# in4_single_v0_2_revB.net
KiCad netlist of a schematic drawn in EAGLE
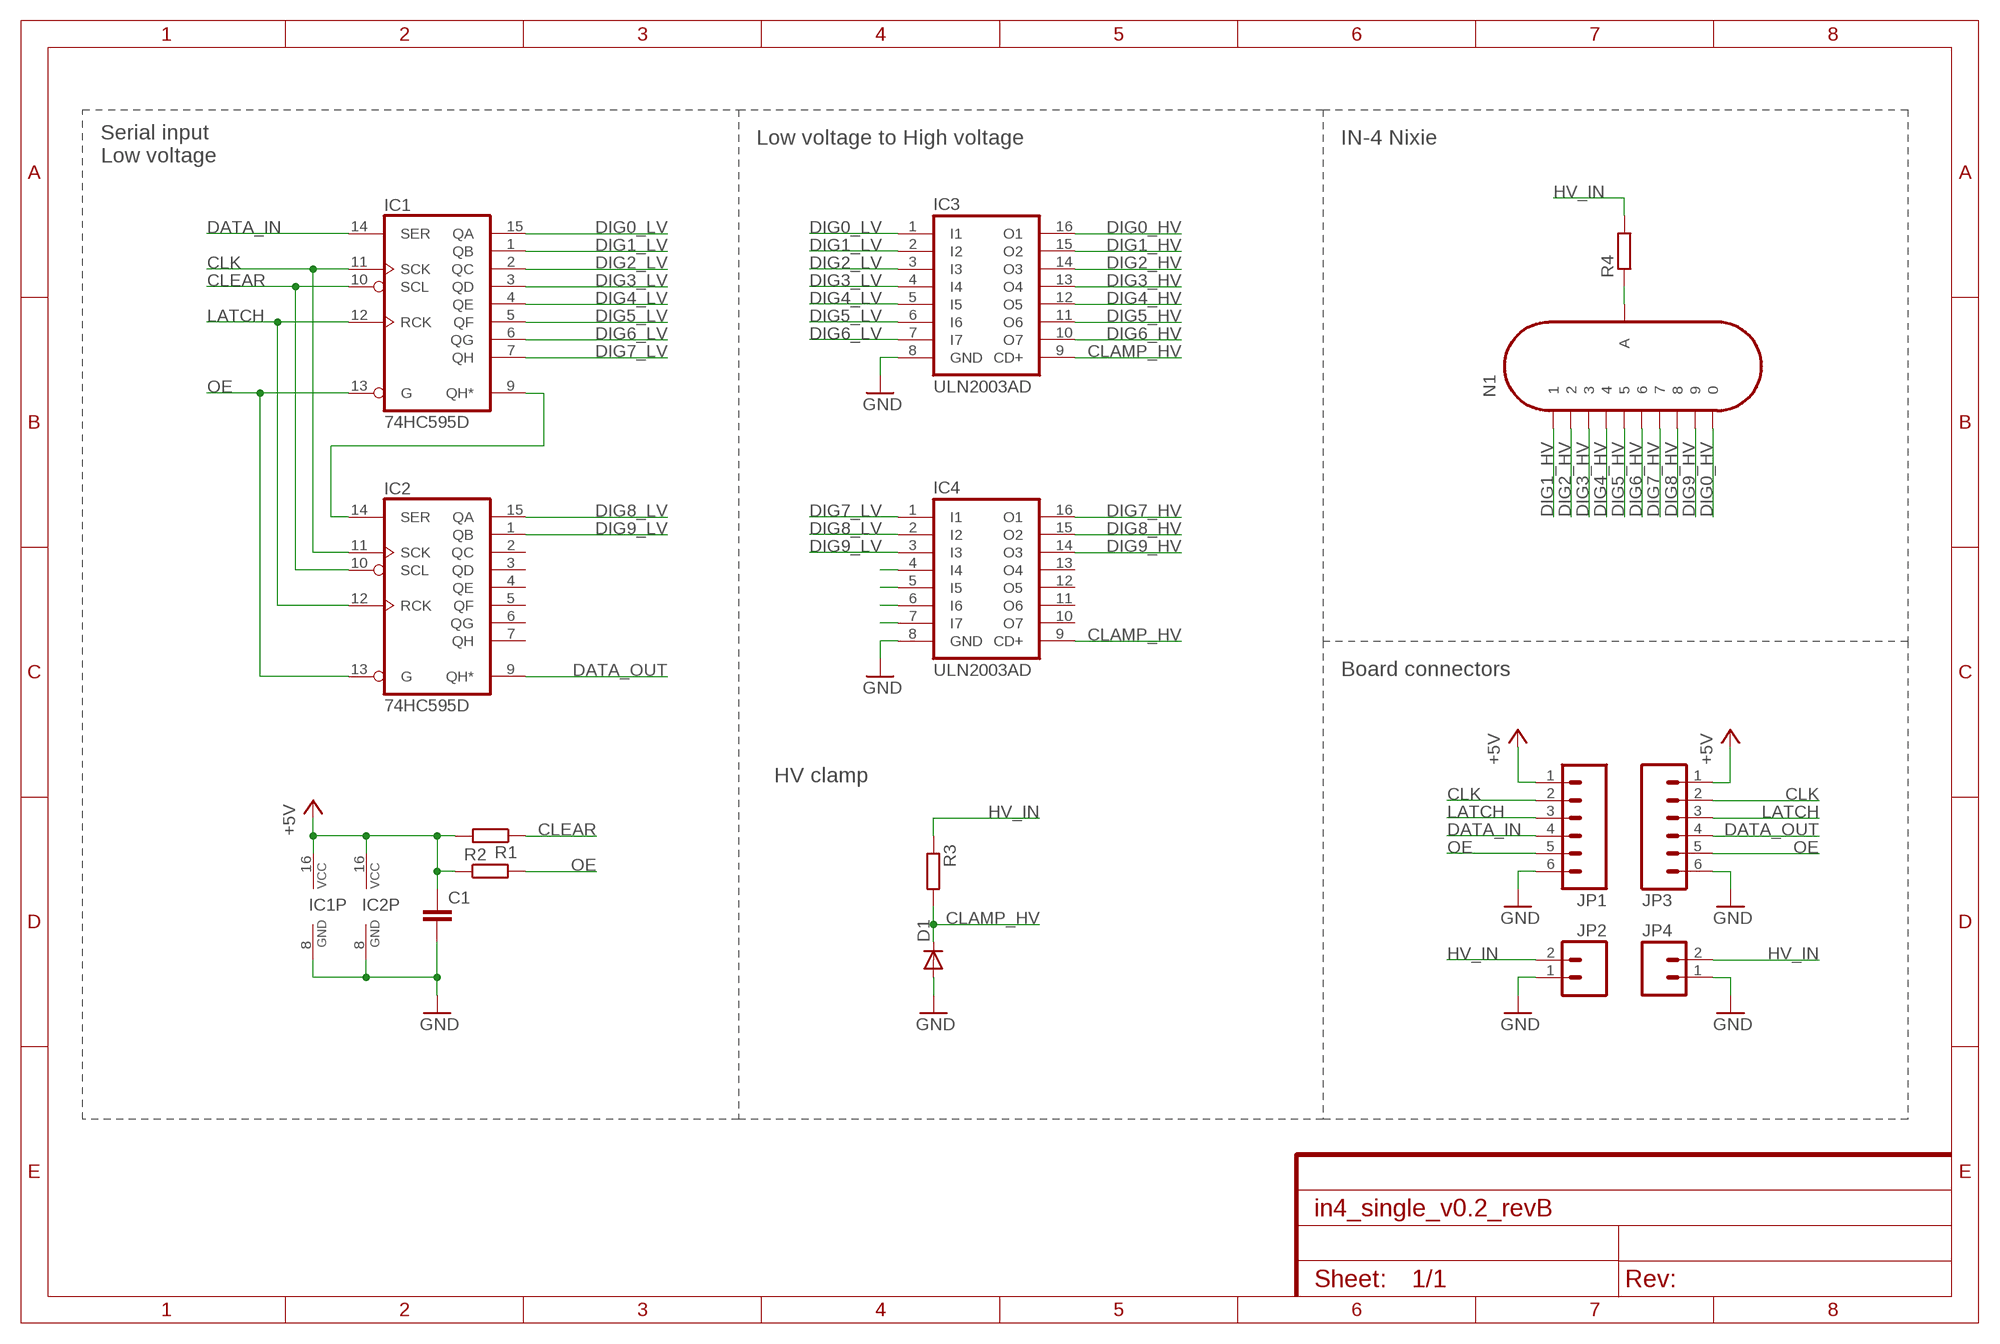
[diagram p0: schematic, sheet 1]

(export (version "E")
  (design (tool "Eeschema 10.0.6"))
  (components
    (comp (ref "C1")
      (value "C-EUC0805")
      (footprint "eagle-import:C0805")
      (libsource (lib "eagle-import") (part "C-EUC0805"))
    )
    (comp (ref "D1")
      (value "DIODE-SOD-123")
      (footprint "eagle-import:SOD-123")
      (libsource (lib "eagle-import") (part "DIODE-SOD-123"))
    )
    (comp (ref "IC1")
      (value "74HC595D")
      (footprint "eagle-import:SO16")
      (libsource (lib "eagle-import") (part "74595DHC"))
    )
    (comp (ref "IC2")
      (value "74HC595D")
      (footprint "eagle-import:SO16")
      (libsource (lib "eagle-import") (part "74595DHC"))
    )
    (comp (ref "IC3")
      (value "ULN2003AD")
      (footprint "eagle-import:SO16")
      (libsource (lib "eagle-import") (part "ULN2003AD"))
    )
    (comp (ref "IC4")
      (value "ULN2003AD")
      (footprint "eagle-import:SO16")
      (libsource (lib "eagle-import") (part "ULN2003AD"))
    )
    (comp (ref "JP1")
      (value "M06NO_SILK_FEMALE_PTH")
      (footprint "eagle-import:1X06_NO_SILK")
      (libsource (lib "eagle-import") (part "M06NO_SILK_FEMALE_PTH"))
    )
    (comp (ref "JP2")
      (value "M021X02_NO_SILK")
      (footprint "eagle-import:1X02_NO_SILK")
      (libsource (lib "eagle-import") (part "M021X02_NO_SILK"))
    )
    (comp (ref "JP3")
      (value "M06NO_SILK_FEMALE_PTH")
      (footprint "eagle-import:1X06_NO_SILK")
      (libsource (lib "eagle-import") (part "M06NO_SILK_FEMALE_PTH"))
    )
    (comp (ref "JP4")
      (value "M021X02_NO_SILK")
      (footprint "eagle-import:1X02_NO_SILK")
      (libsource (lib "eagle-import") (part "M021X02_NO_SILK"))
    )
    (comp (ref "N1")
      (value "IN-4")
      (footprint "eagle-import:IN-4")
      (libsource (lib "eagle-import") (part "IN-4"))
    )
    (comp (ref "R1")
      (value "R-EU_R0805")
      (footprint "eagle-import:R0805")
      (libsource (lib "eagle-import") (part "R-EU_R0805"))
    )
    (comp (ref "R2")
      (value "R-EU_R0805")
      (footprint "eagle-import:R0805")
      (libsource (lib "eagle-import") (part "R-EU_R0805"))
    )
    (comp (ref "R3")
      (value "R-EU_R0805")
      (footprint "eagle-import:R0805")
      (libsource (lib "eagle-import") (part "R-EU_R0805"))
    )
    (comp (ref "R4")
      (value "R-EU_R1210")
      (footprint "eagle-import:R1210")
      (libsource (lib "eagle-import") (part "resistor_R-EU_R1210"))
    )
  )
  (nets
    (net (code "1") (name "+5V") (class "Default")
      (node (ref "C1") (pin "1") (pinfunction "1_1") (pintype "passive"))
      (node (ref "IC1") (pin "16") (pinfunction "VCC_16") (pintype "power_in"))
      (node (ref "IC2") (pin "16") (pinfunction "VCC_16") (pintype "power_in"))
      (node (ref "JP1") (pin "1") (pinfunction "1_1") (pintype "passive"))
      (node (ref "JP3") (pin "1") (pinfunction "1_1") (pintype "passive"))
      (node (ref "R1") (pin "2") (pinfunction "2_2") (pintype "passive"))
      (node (ref "R2") (pin "1") (pinfunction "1_1") (pintype "passive"))
    )
    (net (code "2") (name "/CLAMP_HV") (class "Default")
      (node (ref "D1") (pin "C") (pinfunction "C_C") (pintype "passive"))
      (node (ref "IC3") (pin "9") (pinfunction "CD+_9") (pintype "passive"))
      (node (ref "IC4") (pin "9") (pinfunction "CD+_9") (pintype "passive"))
      (node (ref "R3") (pin "2") (pinfunction "2_2") (pintype "passive"))
    )
    (net (code "3") (name "/CLEAR") (class "Default")
      (node (ref "IC1") (pin "10") (pinfunction "SCL_10") (pintype "input"))
      (node (ref "IC2") (pin "10") (pinfunction "SCL_10") (pintype "input"))
      (node (ref "R1") (pin "1") (pinfunction "1_1") (pintype "passive"))
    )
    (net (code "4") (name "/CLK") (class "Default")
      (node (ref "IC1") (pin "11") (pinfunction "SCK_11") (pintype "input"))
      (node (ref "IC2") (pin "11") (pinfunction "SCK_11") (pintype "input"))
      (node (ref "JP1") (pin "2") (pinfunction "2_2") (pintype "passive"))
      (node (ref "JP3") (pin "2") (pinfunction "2_2") (pintype "passive"))
    )
    (net (code "5") (name "/DATA_IN") (class "Default")
      (node (ref "IC1") (pin "14") (pinfunction "SER_14") (pintype "input"))
      (node (ref "JP1") (pin "4") (pinfunction "4_4") (pintype "passive"))
    )
    (net (code "6") (name "/DATA_OUT") (class "Default")
      (node (ref "IC2") (pin "9") (pinfunction "QH*_9") (pintype "tri_state"))
      (node (ref "JP3") (pin "4") (pinfunction "4_4") (pintype "passive"))
    )
    (net (code "7") (name "/DIG0_HV") (class "Default")
      (node (ref "IC3") (pin "16") (pinfunction "O1_16") (pintype "open_collector"))
      (node (ref "N1") (pin "8") (pinfunction "0_8") (pintype "bidirectional"))
    )
    (net (code "8") (name "/DIG0_LV") (class "Default")
      (node (ref "IC1") (pin "15") (pinfunction "QA_15") (pintype "tri_state"))
      (node (ref "IC3") (pin "1") (pinfunction "I1_1") (pintype "input"))
    )
    (net (code "9") (name "/DIG1_HV") (class "Default")
      (node (ref "IC3") (pin "15") (pinfunction "O2_15") (pintype "open_collector"))
      (node (ref "N1") (pin "14") (pinfunction "1_14") (pintype "bidirectional"))
    )
    (net (code "10") (name "/DIG1_LV") (class "Default")
      (node (ref "IC1") (pin "1") (pinfunction "QB_1") (pintype "tri_state"))
      (node (ref "IC3") (pin "2") (pinfunction "I2_2") (pintype "input"))
    )
    (net (code "11") (name "/DIG2_HV") (class "Default")
      (node (ref "IC3") (pin "14") (pinfunction "O3_14") (pintype "open_collector"))
      (node (ref "N1") (pin "9") (pinfunction "2_9") (pintype "bidirectional"))
    )
    (net (code "12") (name "/DIG2_LV") (class "Default")
      (node (ref "IC1") (pin "2") (pinfunction "QC_2") (pintype "tri_state"))
      (node (ref "IC3") (pin "3") (pinfunction "I3_3") (pintype "input"))
    )
    (net (code "13") (name "/DIG3_HV") (class "Default")
      (node (ref "IC3") (pin "13") (pinfunction "O4_13") (pintype "open_collector"))
      (node (ref "N1") (pin "11") (pinfunction "3_11") (pintype "bidirectional"))
    )
    (net (code "14") (name "/DIG3_LV") (class "Default")
      (node (ref "IC1") (pin "3") (pinfunction "QD_3") (pintype "tri_state"))
      (node (ref "IC3") (pin "4") (pinfunction "I4_4") (pintype "input"))
    )
    (net (code "15") (name "/DIG4_HV") (class "Default")
      (node (ref "IC3") (pin "12") (pinfunction "O5_12") (pintype "open_collector"))
      (node (ref "N1") (pin "1") (pinfunction "4_1") (pintype "bidirectional"))
    )
    (net (code "16") (name "/DIG4_LV") (class "Default")
      (node (ref "IC1") (pin "4") (pinfunction "QE_4") (pintype "tri_state"))
      (node (ref "IC3") (pin "5") (pinfunction "I5_5") (pintype "input"))
    )
    (net (code "17") (name "/DIG5_HV") (class "Default")
      (node (ref "IC3") (pin "11") (pinfunction "O6_11") (pintype "open_collector"))
      (node (ref "N1") (pin "12") (pinfunction "5_12") (pintype "bidirectional"))
    )
    (net (code "18") (name "/DIG5_LV") (class "Default")
      (node (ref "IC1") (pin "5") (pinfunction "QF_5") (pintype "tri_state"))
      (node (ref "IC3") (pin "6") (pinfunction "I6_6") (pintype "input"))
    )
    (net (code "19") (name "/DIG6_HV") (class "Default")
      (node (ref "IC3") (pin "10") (pinfunction "O7_10") (pintype "open_collector"))
      (node (ref "N1") (pin "2") (pinfunction "6_2") (pintype "bidirectional"))
    )
    (net (code "20") (name "/DIG6_LV") (class "Default")
      (node (ref "IC1") (pin "6") (pinfunction "QG_6") (pintype "tri_state"))
      (node (ref "IC3") (pin "7") (pinfunction "I7_7") (pintype "input"))
    )
    (net (code "21") (name "/DIG7_HV") (class "Default")
      (node (ref "IC4") (pin "16") (pinfunction "O1_16") (pintype "open_collector"))
      (node (ref "N1") (pin "6") (pinfunction "7_6") (pintype "bidirectional"))
    )
    (net (code "22") (name "/DIG7_LV") (class "Default")
      (node (ref "IC1") (pin "7") (pinfunction "QH_7") (pintype "tri_state"))
      (node (ref "IC4") (pin "1") (pinfunction "I1_1") (pintype "input"))
    )
    (net (code "23") (name "/DIG8_HV") (class "Default")
      (node (ref "IC4") (pin "15") (pinfunction "O2_15") (pintype "open_collector"))
      (node (ref "N1") (pin "3") (pinfunction "8_3") (pintype "bidirectional"))
    )
    (net (code "24") (name "/DIG8_LV") (class "Default")
      (node (ref "IC2") (pin "15") (pinfunction "QA_15") (pintype "tri_state"))
      (node (ref "IC4") (pin "2") (pinfunction "I2_2") (pintype "input"))
    )
    (net (code "25") (name "/DIG9_HV") (class "Default")
      (node (ref "IC4") (pin "14") (pinfunction "O3_14") (pintype "open_collector"))
      (node (ref "N1") (pin "5") (pinfunction "9_5") (pintype "bidirectional"))
    )
    (net (code "26") (name "/DIG9_LV") (class "Default")
      (node (ref "IC2") (pin "1") (pinfunction "QB_1") (pintype "tri_state"))
      (node (ref "IC4") (pin "3") (pinfunction "I3_3") (pintype "input"))
    )
    (net (code "27") (name "/HV_IN") (class "Default")
      (node (ref "JP2") (pin "2") (pinfunction "2_2") (pintype "passive"))
      (node (ref "JP4") (pin "2") (pinfunction "2_2") (pintype "passive"))
      (node (ref "R3") (pin "1") (pinfunction "1_1") (pintype "passive"))
      (node (ref "R4") (pin "2") (pinfunction "2_2") (pintype "passive"))
    )
    (net (code "28") (name "/LATCH") (class "Default")
      (node (ref "IC1") (pin "12") (pinfunction "RCK_12") (pintype "input"))
      (node (ref "IC2") (pin "12") (pinfunction "RCK_12") (pintype "input"))
      (node (ref "JP1") (pin "3") (pinfunction "3_3") (pintype "passive"))
      (node (ref "JP3") (pin "3") (pinfunction "3_3") (pintype "passive"))
    )
    (net (code "29") (name "/OE") (class "Default")
      (node (ref "IC1") (pin "13") (pinfunction "G_13") (pintype "input"))
      (node (ref "IC2") (pin "13") (pinfunction "G_13") (pintype "input"))
      (node (ref "JP1") (pin "5") (pinfunction "5_5") (pintype "passive"))
      (node (ref "JP3") (pin "5") (pinfunction "5_5") (pintype "passive"))
      (node (ref "R2") (pin "2") (pinfunction "2_2") (pintype "passive"))
    )
    (net (code "30") (name "GND") (class "Default")
      (node (ref "C1") (pin "2") (pinfunction "2_2") (pintype "passive"))
      (node (ref "D1") (pin "A") (pinfunction "A_A") (pintype "passive"))
      (node (ref "IC1") (pin "8") (pinfunction "GND_8") (pintype "power_in"))
      (node (ref "IC2") (pin "8") (pinfunction "GND_8") (pintype "power_in"))
      (node (ref "IC3") (pin "8") (pinfunction "GND_8") (pintype "power_in"))
      (node (ref "IC4") (pin "8") (pinfunction "GND_8") (pintype "power_in"))
      (node (ref "JP1") (pin "6") (pinfunction "6_6") (pintype "passive"))
      (node (ref "JP2") (pin "1") (pinfunction "1_1") (pintype "passive"))
      (node (ref "JP3") (pin "6") (pinfunction "6_6") (pintype "passive"))
      (node (ref "JP4") (pin "1") (pinfunction "1_1") (pintype "passive"))
    )
    (net (code "31") (name "Net-(IC1A-QH*)") (class "Default")
      (node (ref "IC1") (pin "9") (pinfunction "QH*_9") (pintype "tri_state"))
      (node (ref "IC2") (pin "14") (pinfunction "SER_14") (pintype "input"))
    )
    (net (code "32") (name "Net-(N1-A)") (class "Default")
      (node (ref "N1") (pin "4") (pinfunction "A_4") (pintype "bidirectional"))
      (node (ref "R4") (pin "1") (pinfunction "1_1") (pintype "passive"))
    )
    (net (code "33") (name "unconnected-(IC2A-QC-Pad2)") (class "Default")
      (node (ref "IC2") (pin "2") (pinfunction "QC_2") (pintype "tri_state"))
    )
    (net (code "34") (name "unconnected-(IC2A-QD-Pad3)") (class "Default")
      (node (ref "IC2") (pin "3") (pinfunction "QD_3") (pintype "tri_state"))
    )
    (net (code "35") (name "unconnected-(IC2A-QE-Pad4)") (class "Default")
      (node (ref "IC2") (pin "4") (pinfunction "QE_4") (pintype "tri_state"))
    )
    (net (code "36") (name "unconnected-(IC2A-QF-Pad5)") (class "Default")
      (node (ref "IC2") (pin "5") (pinfunction "QF_5") (pintype "tri_state"))
    )
    (net (code "37") (name "unconnected-(IC2A-QG-Pad6)") (class "Default")
      (node (ref "IC2") (pin "6") (pinfunction "QG_6") (pintype "tri_state"))
    )
    (net (code "38") (name "unconnected-(IC2A-QH-Pad7)") (class "Default")
      (node (ref "IC2") (pin "7") (pinfunction "QH_7") (pintype "tri_state"))
    )
    (net (code "39") (name "unconnected-(IC4-I4-Pad4)") (class "Default")
      (node (ref "IC4") (pin "4") (pinfunction "I4_4") (pintype "input"))
    )
    (net (code "40") (name "unconnected-(IC4-I5-Pad5)") (class "Default")
      (node (ref "IC4") (pin "5") (pinfunction "I5_5") (pintype "input"))
    )
    (net (code "41") (name "unconnected-(IC4-I6-Pad6)") (class "Default")
      (node (ref "IC4") (pin "6") (pinfunction "I6_6") (pintype "input"))
    )
    (net (code "42") (name "unconnected-(IC4-I7-Pad7)") (class "Default")
      (node (ref "IC4") (pin "7") (pinfunction "I7_7") (pintype "input"))
    )
    (net (code "43") (name "unconnected-(IC4-O4-Pad13)") (class "Default")
      (node (ref "IC4") (pin "13") (pinfunction "O4_13") (pintype "open_collector"))
    )
    (net (code "44") (name "unconnected-(IC4-O5-Pad12)") (class "Default")
      (node (ref "IC4") (pin "12") (pinfunction "O5_12") (pintype "open_collector"))
    )
    (net (code "45") (name "unconnected-(IC4-O6-Pad11)") (class "Default")
      (node (ref "IC4") (pin "11") (pinfunction "O6_11") (pintype "open_collector"))
    )
    (net (code "46") (name "unconnected-(IC4-O7-Pad10)") (class "Default")
      (node (ref "IC4") (pin "10") (pinfunction "O7_10") (pintype "open_collector"))
    )
  )
)
